# lm3410-boost-flashlight-driver-17mm-mk-1.net
KiCad netlist of a schematic drawn in EAGLE
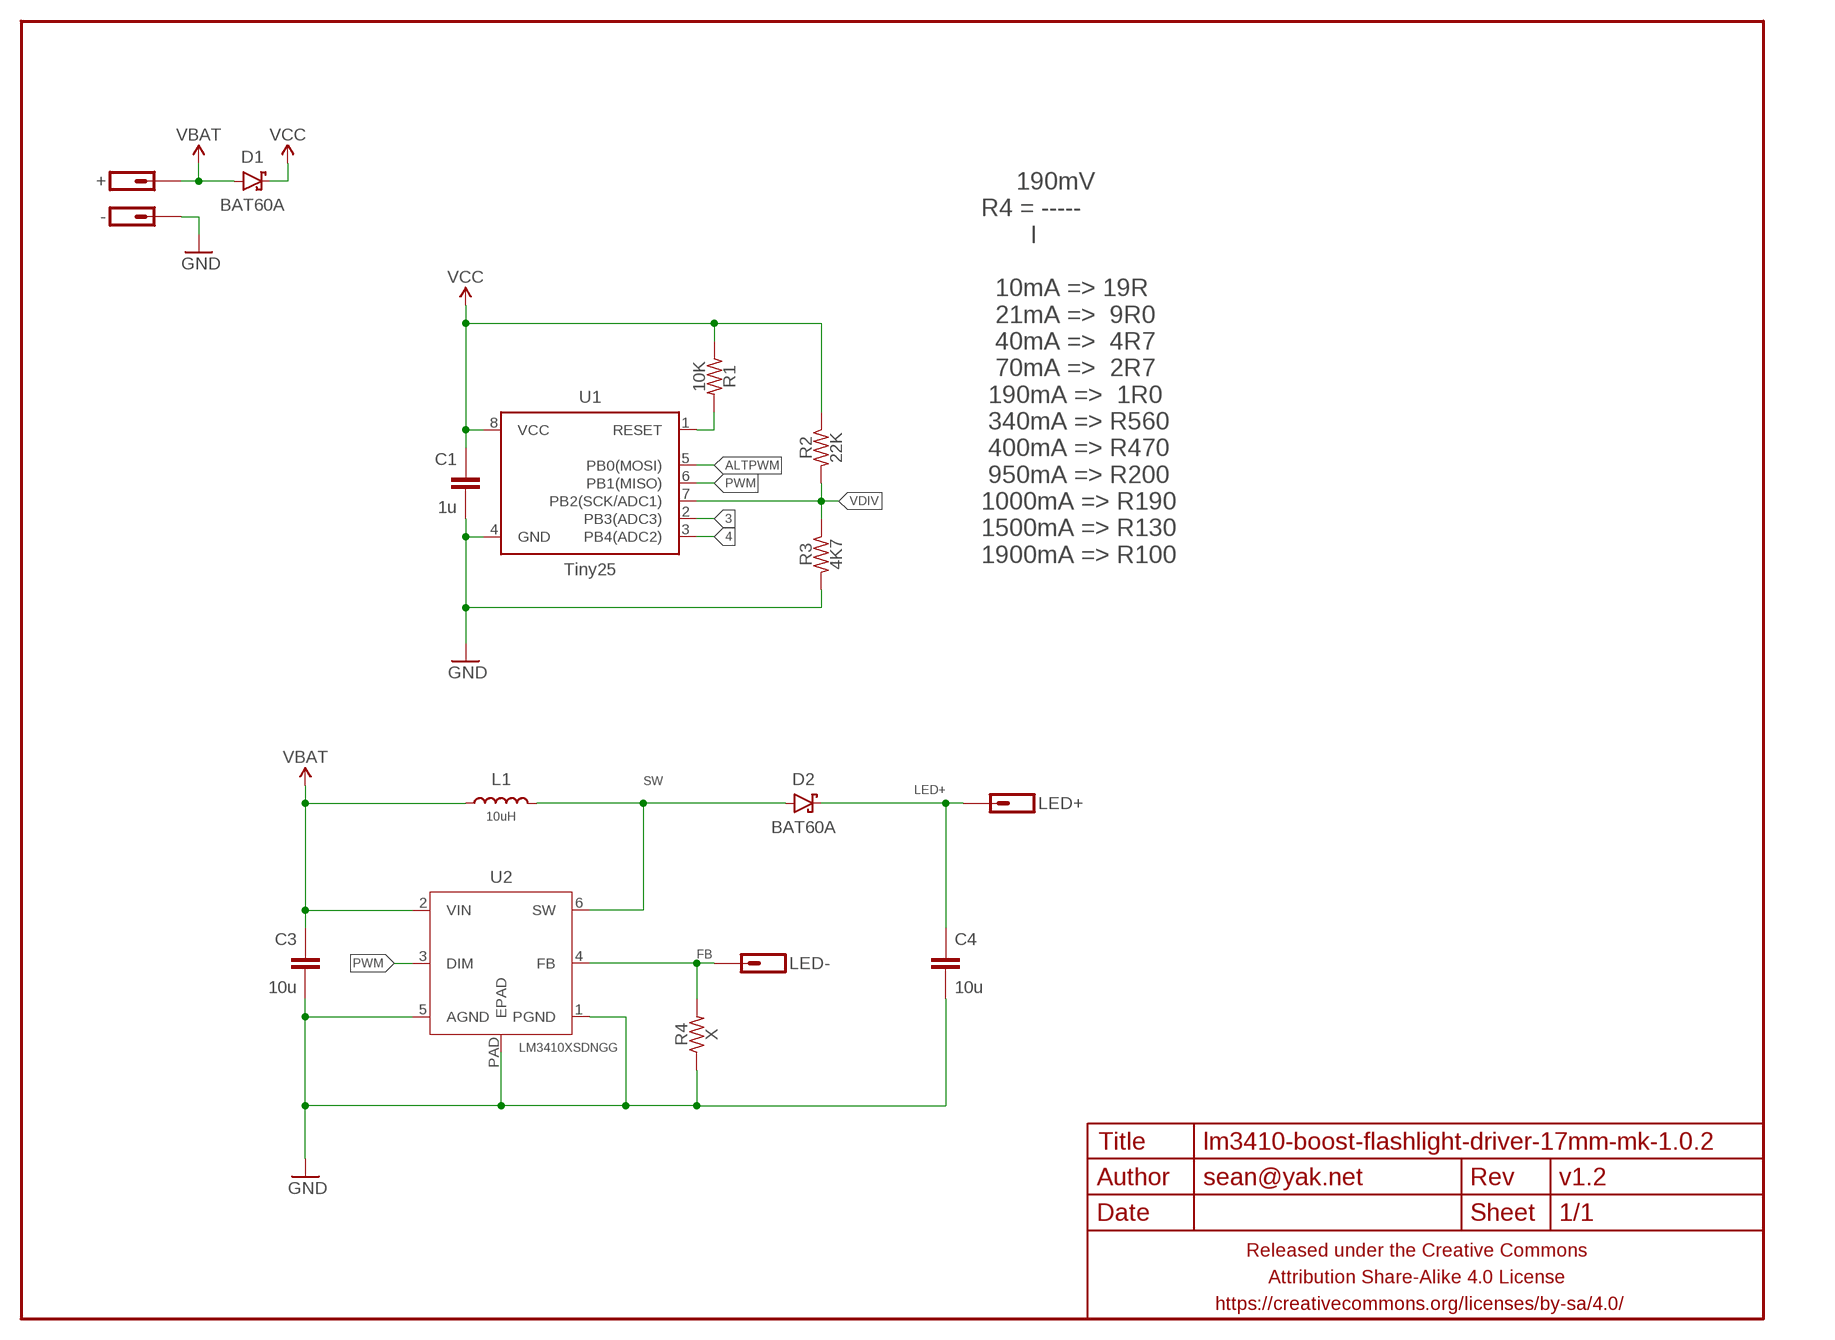
[diagram p0: schematic, sheet 1]

(export (version "E")
  (design (tool "Eeschema 10.0.6"))
  (components
    (comp (ref "+")
      (value "M01PTH-1MM-CIR-NS")
      (footprint "eagle-import:1X01-1MM-CIR-NS")
      (libsource (lib "eagle-import") (part "M01PTH-1MM-CIR-NS"))
    )
    (comp (ref "-")
      (value "M01NOT-A-VIA-NOPE")
      (footprint "eagle-import:1X01_NOSILK_NOSTOP")
      (libsource (lib "eagle-import") (part "M01NOT-A-VIA-NOPE"))
    )
    (comp (ref "C1")
      (value "1u")
      (footprint "eagle-import:C0402")
      (libsource (lib "eagle-import") (part "CAPACITOR-CERAMICC0402"))
    )
    (comp (ref "C3")
      (value "10u")
      (footprint "eagle-import:C0805-TIGHTER")
      (libsource (lib "eagle-import") (part "CAPACITOR-CERAMICC0805-TIGHTER"))
    )
    (comp (ref "C4")
      (value "10u")
      (footprint "eagle-import:C0805-TIGHTER")
      (libsource (lib "eagle-import") (part "CAPACITOR-CERAMICC0805-TIGHTER"))
    )
    (comp (ref "D1")
      (value "BAT60A")
      (footprint "eagle-import:SOD323-SCHOTTKY")
      (libsource (lib "eagle-import") (part "DIODE-SCHOTTKYSOD323"))
    )
    (comp (ref "D2")
      (value "BAT60A")
      (footprint "eagle-import:SOD323-SCHOTTKY")
      (libsource (lib "eagle-import") (part "DIODE-SCHOTTKYSOD323"))
    )
    (comp (ref "FRAME1")
      (value "FRAME-LETTERNO_PACKAGE")
      (footprint "eagle-import:DUMMY")
      (fields (field (name "DESIGNER") "sean@yak.net") (field (name "VERSION") "v1.2"))
      (libsource (lib "eagle-import") (part "FRAME-LETTERNO_PACKAGE"))
    )
    (comp (ref "L1")
      (value "10uH")
      (footprint "eagle-import:XFL4020")
      (libsource (lib "eagle-import") (part "INDUCTORXFL4020"))
    )
    (comp (ref "LED+")
      (value "M01PTH-1MM-CIR-NS")
      (footprint "eagle-import:1X01-1MM-CIR-NS")
      (libsource (lib "eagle-import") (part "M01PTH-1MM-CIR-NS"))
    )
    (comp (ref "LED-")
      (value "M01PTH-1MM-CIR-NS")
      (footprint "eagle-import:1X01-1MM-CIR-NS")
      (libsource (lib "eagle-import") (part "M01PTH-1MM-CIR-NS"))
    )
    (comp (ref "R1")
      (value "10K")
      (footprint "eagle-import:R0402")
      (libsource (lib "eagle-import") (part "RESISTORR0402"))
    )
    (comp (ref "R2")
      (value "22K")
      (footprint "eagle-import:R0402")
      (libsource (lib "eagle-import") (part "RESISTORR0402"))
    )
    (comp (ref "R3")
      (value "4K7")
      (footprint "eagle-import:R0402")
      (libsource (lib "eagle-import") (part "RESISTORR0402"))
    )
    (comp (ref "R4")
      (value "X")
      (footprint "eagle-import:R0805-TIGHTER")
      (libsource (lib "eagle-import") (part "RESISTORR0805-TIGHTER"))
    )
    (comp (ref "U1")
      (value "Tiny25")
      (footprint "eagle-import:SO08-SKINNYPADS")
      (libsource (lib "eagle-import") (part "ATTINY45TINY25-SOICN-NARROWER"))
    )
    (comp (ref "U2")
      (value "LM3410XSDNGG")
      (footprint "eagle-import:DFN300X300X80-7N")
      (fields (field (name "MPN") "LM3410XSD"))
      (libsource (lib "eagle-import") (part "LM3410XSDNGG"))
    )
  )
  (nets
    (net (code "1") (name "/FB") (class "Default")
      (node (ref "LED-") (pin "1") (pinfunction "1_1") (pintype "passive"))
      (node (ref "R4") (pin "2") (pinfunction "2_2") (pintype "passive"))
      (node (ref "U2") (pin "4") (pinfunction "FB_4") (pintype "input"))
    )
    (net (code "2") (name "/LED+") (class "Default")
      (node (ref "C4") (pin "1") (pinfunction "1_1") (pintype "passive"))
      (node (ref "D2") (pin "C") (pinfunction "C_C") (pintype "passive"))
      (node (ref "LED+") (pin "1") (pinfunction "1_1") (pintype "passive"))
    )
    (net (code "3") (name "/SW") (class "Default")
      (node (ref "D2") (pin "A") (pinfunction "A_A") (pintype "passive"))
      (node (ref "L1") (pin "P$2") (pinfunction "2_P$2") (pintype "passive"))
      (node (ref "U2") (pin "6") (pinfunction "SW_6") (pintype "output"))
    )
    (net (code "4") (name "3") (class "Default")
      (node (ref "U1") (pin "2") (pinfunction "PB3(ADC3)_2") (pintype "bidirectional"))
    )
    (net (code "5") (name "4") (class "Default")
      (node (ref "U1") (pin "3") (pinfunction "PB4(ADC2)_3") (pintype "bidirectional"))
    )
    (net (code "6") (name "ALTPWM") (class "Default")
      (node (ref "U1") (pin "5") (pinfunction "PB0(MOSI)_5") (pintype "bidirectional"))
    )
    (net (code "7") (name "GND") (class "Default")
      (node (ref "-") (pin "P$1") (pinfunction "1_P$1") (pintype "passive"))
      (node (ref "C1") (pin "2") (pinfunction "2_2") (pintype "passive"))
      (node (ref "C3") (pin "2") (pinfunction "2_2") (pintype "passive"))
      (node (ref "C4") (pin "2") (pinfunction "2_2") (pintype "passive"))
      (node (ref "R3") (pin "2") (pinfunction "2_2") (pintype "passive"))
      (node (ref "R4") (pin "1") (pinfunction "1_1") (pintype "passive"))
      (node (ref "U1") (pin "4") (pinfunction "GND_4") (pintype "bidirectional"))
      (node (ref "U2") (pin "1") (pinfunction "PGND_1") (pintype "passive"))
      (node (ref "U2") (pin "5") (pinfunction "AGND_5") (pintype "passive"))
      (node (ref "U2") (pin "PAD") (pinfunction "EPAD_PAD") (pintype "passive"))
    )
    (net (code "8") (name "Net-(U1-RESET)") (class "Default")
      (node (ref "R1") (pin "2") (pinfunction "2_2") (pintype "passive"))
      (node (ref "U1") (pin "1") (pinfunction "RESET_1") (pintype "bidirectional"))
    )
    (net (code "9") (name "PWM") (class "Default")
      (node (ref "U1") (pin "6") (pinfunction "PB1(MISO)_6") (pintype "bidirectional"))
      (node (ref "U2") (pin "3") (pinfunction "DIM_3") (pintype "input"))
    )
    (net (code "10") (name "VBAT") (class "Default")
      (node (ref "+") (pin "1") (pinfunction "1_1") (pintype "passive"))
      (node (ref "C3") (pin "1") (pinfunction "1_1") (pintype "passive"))
      (node (ref "D1") (pin "A") (pinfunction "A_A") (pintype "passive"))
      (node (ref "L1") (pin "P$1") (pinfunction "1_P$1") (pintype "passive"))
      (node (ref "U2") (pin "2") (pinfunction "VIN_2") (pintype "power_in"))
    )
    (net (code "11") (name "VCC") (class "Default")
      (node (ref "C1") (pin "1") (pinfunction "1_1") (pintype "passive"))
      (node (ref "D1") (pin "C") (pinfunction "C_C") (pintype "passive"))
      (node (ref "R1") (pin "1") (pinfunction "1_1") (pintype "passive"))
      (node (ref "R2") (pin "1") (pinfunction "1_1") (pintype "passive"))
      (node (ref "U1") (pin "8") (pinfunction "VCC_8") (pintype "bidirectional"))
    )
    (net (code "12") (name "VDIV") (class "Default")
      (node (ref "R2") (pin "2") (pinfunction "2_2") (pintype "passive"))
      (node (ref "R3") (pin "1") (pinfunction "1_1") (pintype "passive"))
      (node (ref "U1") (pin "7") (pinfunction "PB2(SCK/ADC1)_7") (pintype "bidirectional"))
    )
  )
)
